# Openbook_Schematic.net
KiCad netlist of a schematic drawn in EAGLE
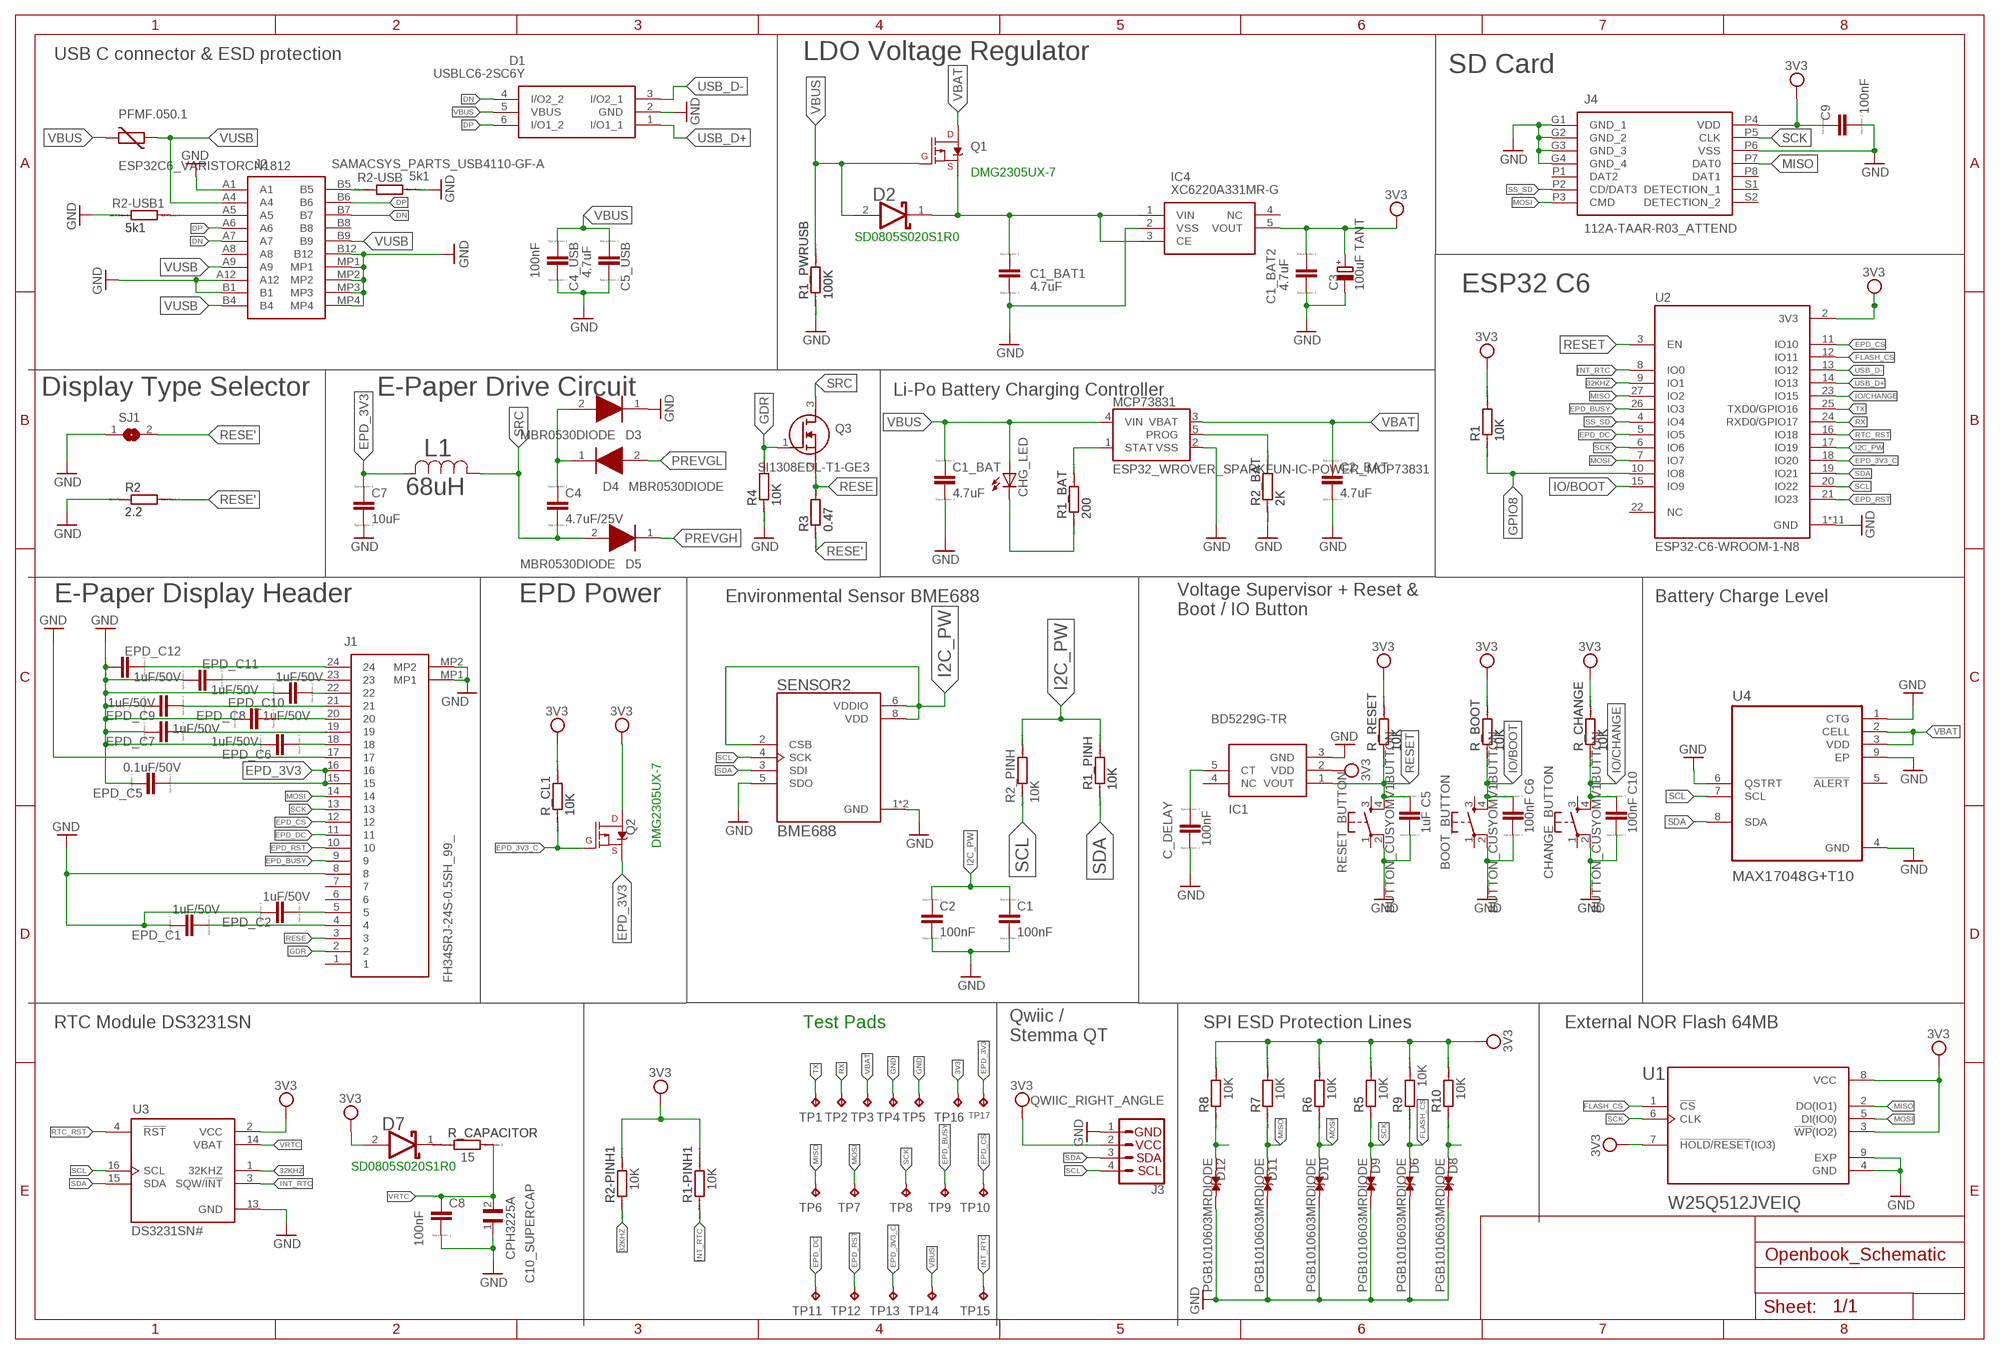
[diagram p0: schematic, sheet 1]

(export (version "E")
  (design (tool "Eeschema 10.0.6"))
  (components
    (comp (ref "BOOT_BUTTON")
      (value "BUTTON_CUSYOMV1BUTTON")
      (footprint "eagle-import:MYBUTTON")
      (libsource (lib "eagle-import") (part "BUTTON_CUSYOMV1BUTTON"))
    )
    (comp (ref "C1")
      (value "100nF")
      (footprint "eagle-import:EAGLE-LTSPICE_C0402")
      (libsource (lib "eagle-import") (part "ESP32_WROVER_EAGLE-LTSPICE_CC0402"))
    )
    (comp (ref "C1_BAT")
      (value "4.7uF")
      (footprint "eagle-import:EAGLE-LTSPICE_C0402")
      (libsource (lib "eagle-import") (part "ESP32_WROVER_EAGLE-LTSPICE_CC0402"))
    )
    (comp (ref "C1_BAT1")
      (value "4.7uF")
      (footprint "eagle-import:EAGLE-LTSPICE_C0402")
      (libsource (lib "eagle-import") (part "ESP32_WROVER_EAGLE-LTSPICE_CC0402"))
    )
    (comp (ref "C1_BAT2")
      (value "4.7uF")
      (footprint "eagle-import:EAGLE-LTSPICE_C0402")
      (libsource (lib "eagle-import") (part "ESP32_WROVER_EAGLE-LTSPICE_CC0402"))
    )
    (comp (ref "C2")
      (value "100nF")
      (footprint "eagle-import:EAGLE-LTSPICE_C0402")
      (libsource (lib "eagle-import") (part "ESP32_WROVER_EAGLE-LTSPICE_CC0402"))
    )
    (comp (ref "C2_BAT")
      (value "4.7uF")
      (footprint "eagle-import:EAGLE-LTSPICE_C0402")
      (libsource (lib "eagle-import") (part "ESP32_WROVER_EAGLE-LTSPICE_CC0402"))
    )
    (comp (ref "C3")
      (value "100uF TANT")
      (footprint "eagle-import:RCL_CT3528")
      (libsource (lib "eagle-import") (part "RCL_CPOL-EUCT3528"))
    )
    (comp (ref "C4")
      (value "4.7uF/25V")
      (footprint "eagle-import:EAGLE-LTSPICE_C0402")
      (libsource (lib "eagle-import") (part "ESP32_WROVER_EAGLE-LTSPICE_CC0402"))
    )
    (comp (ref "C4_USB")
      (value "100nF")
      (footprint "eagle-import:EAGLE-LTSPICE_C0402")
      (libsource (lib "eagle-import") (part "ESP32_WROVER_EAGLE-LTSPICE_CC0402"))
    )
    (comp (ref "C5")
      (value "1uF")
      (footprint "eagle-import:EAGLE-LTSPICE_C0402")
      (libsource (lib "eagle-import") (part "ESP32_WROVER_EAGLE-LTSPICE_CC0402"))
    )
    (comp (ref "C5_USB")
      (value "4.7uF")
      (footprint "eagle-import:EAGLE-LTSPICE_C0402")
      (libsource (lib "eagle-import") (part "ESP32_WROVER_EAGLE-LTSPICE_CC0402"))
    )
    (comp (ref "C6")
      (value "100nF")
      (footprint "eagle-import:EAGLE-LTSPICE_C0402")
      (libsource (lib "eagle-import") (part "ESP32_WROVER_EAGLE-LTSPICE_CC0402"))
    )
    (comp (ref "C7")
      (value "10uF")
      (footprint "eagle-import:EAGLE-LTSPICE_C0402")
      (libsource (lib "eagle-import") (part "ESP32_WROVER_EAGLE-LTSPICE_CC0402"))
    )
    (comp (ref "C8")
      (value "100nF")
      (footprint "eagle-import:EAGLE-LTSPICE_C0402")
      (libsource (lib "eagle-import") (part "ESP32_WROVER_EAGLE-LTSPICE_CC0402"))
    )
    (comp (ref "C9")
      (value "100nF")
      (footprint "eagle-import:EAGLE-LTSPICE_C0402")
      (libsource (lib "eagle-import") (part "ESP32_WROVER_EAGLE-LTSPICE_CC0402"))
    )
    (comp (ref "C10")
      (value "100nF")
      (footprint "eagle-import:EAGLE-LTSPICE_C0402")
      (libsource (lib "eagle-import") (part "ESP32_WROVER_EAGLE-LTSPICE_CC0402"))
    )
    (comp (ref "C10_SUPERCAP")
      (value "CPH3225A")
      (footprint "eagle-import:CAPCP3225X100N")
      (fields (field (name "MF") "Seiko Instruments"))
      (libsource (lib "eagle-import") (part "CPH3225A"))
    )
    (comp (ref "CHANGE_BUTTON")
      (value "BUTTON_CUSYOMV1BUTTON")
      (footprint "eagle-import:MYBUTTON")
      (libsource (lib "eagle-import") (part "BUTTON_CUSYOMV1BUTTON"))
    )
    (comp (ref "CHG_LED")
      (value "ADAFRUIT_LEDCHIP-LED0603")
      (footprint "eagle-import:ADAFRUIT_CHIP-LED0603")
      (libsource (lib "eagle-import") (part "ADAFRUIT_LEDCHIP-LED0603"))
    )
    (comp (ref "C_DELAY")
      (value "100nF")
      (footprint "eagle-import:EAGLE-LTSPICE_C0402")
      (libsource (lib "eagle-import") (part "ESP32_WROVER_EAGLE-LTSPICE_CC0402"))
    )
    (comp (ref "D1")
      (value "USBLC6-2SC6Y")
      (footprint "eagle-import:SOT95P280X145-6N")
      (fields (field (name "MF") "STMicroelectronics"))
      (libsource (lib "eagle-import") (part "USBLC6-2SC6Y"))
    )
    (comp (ref "D2")
      (value "SD0805S020S1R0")
      (footprint "eagle-import:ESP32_WROVER_AVX---SD0805S020S1R0_AVX_SD0805S020S1R0_0")
      (fields
        (field (name "DIGIKEY_PART_NUMBER") "478-7800-1-ND")
        (field (name "MF") "AVX")
        (field (name "MOUSER_PART_NUMBER") "581-SD0805S020S1R0")
      )
      (libsource (lib "eagle-import") (part "ESP32_WROVER_AVX---SD0805S020S1R0_AVX_SD0805S020S1R0_0_0AVX_SD0805S020S1R0_0_0"))
    )
    (comp (ref "D3")
      (value "MBR0530DIODE")
      (footprint "eagle-import:SOD3716X135N")
      (libsource (lib "eagle-import") (part "MBR0530DIODE"))
    )
    (comp (ref "D4")
      (value "MBR0530DIODE")
      (footprint "eagle-import:SOD3716X135N")
      (libsource (lib "eagle-import") (part "MBR0530DIODE"))
    )
    (comp (ref "D5")
      (value "MBR0530DIODE")
      (footprint "eagle-import:SOD3716X135N")
      (libsource (lib "eagle-import") (part "MBR0530DIODE"))
    )
    (comp (ref "D6")
      (value "PGB1010603MRDIODE")
      (footprint "eagle-import:DIOC1608X36N")
      (libsource (lib "eagle-import") (part "PGB1010603MRDIODE"))
    )
    (comp (ref "D7")
      (value "SD0805S020S1R0")
      (footprint "eagle-import:ESP32_WROVER_AVX---SD0805S020S1R0_AVX_SD0805S020S1R0_0")
      (fields
        (field (name "DIGIKEY_PART_NUMBER") "478-7800-1-ND")
        (field (name "MF") "AVX")
        (field (name "MOUSER_PART_NUMBER") "581-SD0805S020S1R0")
      )
      (libsource (lib "eagle-import") (part "ESP32_WROVER_AVX---SD0805S020S1R0_AVX_SD0805S020S1R0_0_0AVX_SD0805S020S1R0_0_0"))
    )
    (comp (ref "D8")
      (value "PGB1010603MRDIODE")
      (footprint "eagle-import:DIOC1608X36N")
      (libsource (lib "eagle-import") (part "PGB1010603MRDIODE"))
    )
    (comp (ref "D9")
      (value "PGB1010603MRDIODE")
      (footprint "eagle-import:DIOC1608X36N")
      (libsource (lib "eagle-import") (part "PGB1010603MRDIODE"))
    )
    (comp (ref "D10")
      (value "PGB1010603MRDIODE")
      (footprint "eagle-import:DIOC1608X36N")
      (libsource (lib "eagle-import") (part "PGB1010603MRDIODE"))
    )
    (comp (ref "D11")
      (value "PGB1010603MRDIODE")
      (footprint "eagle-import:DIOC1608X36N")
      (libsource (lib "eagle-import") (part "PGB1010603MRDIODE"))
    )
    (comp (ref "D12")
      (value "PGB1010603MRDIODE")
      (footprint "eagle-import:DIOC1608X36N")
      (libsource (lib "eagle-import") (part "PGB1010603MRDIODE"))
    )
    (comp (ref "EPD_C1")
      (value "1uF/50V")
      (footprint "eagle-import:EAGLE-LTSPICE_C0402")
      (libsource (lib "eagle-import") (part "ESP32_WROVER_EAGLE-LTSPICE_CC0402"))
    )
    (comp (ref "EPD_C2")
      (value "1uF/50V")
      (footprint "eagle-import:EAGLE-LTSPICE_C0402")
      (libsource (lib "eagle-import") (part "ESP32_WROVER_EAGLE-LTSPICE_CC0402"))
    )
    (comp (ref "EPD_C5")
      (value "0.1uF/50V")
      (footprint "eagle-import:EAGLE-LTSPICE_C0402")
      (libsource (lib "eagle-import") (part "ESP32_WROVER_EAGLE-LTSPICE_CC0402"))
    )
    (comp (ref "EPD_C6")
      (value "1uF/50V")
      (footprint "eagle-import:EAGLE-LTSPICE_C0402")
      (libsource (lib "eagle-import") (part "ESP32_WROVER_EAGLE-LTSPICE_CC0402"))
    )
    (comp (ref "EPD_C7")
      (value "1uF/50V")
      (footprint "eagle-import:EAGLE-LTSPICE_C0402")
      (libsource (lib "eagle-import") (part "ESP32_WROVER_EAGLE-LTSPICE_CC0402"))
    )
    (comp (ref "EPD_C8")
      (value "1uF/50V")
      (footprint "eagle-import:EAGLE-LTSPICE_C0402")
      (libsource (lib "eagle-import") (part "ESP32_WROVER_EAGLE-LTSPICE_CC0402"))
    )
    (comp (ref "EPD_C9")
      (value "1uF/50V")
      (footprint "eagle-import:EAGLE-LTSPICE_C0402")
      (libsource (lib "eagle-import") (part "ESP32_WROVER_EAGLE-LTSPICE_CC0402"))
    )
    (comp (ref "EPD_C10")
      (value "1uF/50V")
      (footprint "eagle-import:EAGLE-LTSPICE_C0402")
      (libsource (lib "eagle-import") (part "ESP32_WROVER_EAGLE-LTSPICE_CC0402"))
    )
    (comp (ref "EPD_C11")
      (value "1uF/50V")
      (footprint "eagle-import:EAGLE-LTSPICE_C0402")
      (libsource (lib "eagle-import") (part "ESP32_WROVER_EAGLE-LTSPICE_CC0402"))
    )
    (comp (ref "EPD_C12")
      (value "1uF/50V")
      (footprint "eagle-import:EAGLE-LTSPICE_C0402")
      (libsource (lib "eagle-import") (part "ESP32_WROVER_EAGLE-LTSPICE_CC0402"))
    )
    (comp (ref "IC1")
      (value "BD5229G-TR")
      (footprint "eagle-import:SOT95P280X125-5N")
      (fields (field (name "MOUSER_PART_NUMBER") "755-BD5229G-TR"))
      (libsource (lib "eagle-import") (part "BD5229G-TR"))
    )
    (comp (ref "IC4")
      (value "XC6220A331MR-G")
      (footprint "eagle-import:SOT95P280X120-5N")
      (fields (field (name "MOUSER_PART_NUMBER") "865-XC6220A331MR-G"))
      (libsource (lib "eagle-import") (part "XC6220A331MR-G"))
    )
    (comp (ref "J1")
      (value "FH34SRJ-24S-0.5SH_99_")
      (footprint "eagle-import:FH34SRJ24S05SH99")
      (fields
        (field (name "MANUFACTURER_PART_NUMBER") "FH34SRJ-24S-0.5SH(99)")
        (field (name "MOUSER_PART_NUMBER") "798-FH34SRJ24S05SH99")
      )
      (libsource (lib "eagle-import") (part "FH34SRJ-24S-0.5SH_99_"))
    )
    (comp (ref "J2")
      (value "SAMACSYS_PARTS_USB4110-GF-A")
      (footprint "eagle-import:SAMACSYS_PARTS_USB4110GFA")
      (fields
        (field (name "MANUFACTURER_PART_NUMBER") "USB4110-GF-A")
        (field (name "MOUSER_PART_NUMBER") "640-USB4110-GF-A")
      )
      (libsource (lib "eagle-import") (part "SAMACSYS_PARTS_USB4110-GF-A"))
    )
    (comp (ref "J3")
      (value "QWIIC_RIGHT_ANGLE")
      (footprint "eagle-import:JST04_1MM_RA")
      (libsource (lib "eagle-import") (part "QWIIC_CONNECTORJS-1MM"))
    )
    (comp (ref "J4")
      (value "112A-TAAR-R03_ATTEND")
      (footprint "eagle-import:112ATAARR03ATTEND")
      (fields (field (name "MANUFACTURER_PART_NUMBER") "112A-TAAR-R03 ATTEND"))
      (libsource (lib "eagle-import") (part "112A-TAAR-R03_ATTEND"))
    )
    (comp (ref "L1")
      (value "68uH")
      (footprint "eagle-import:IND_4828-WE-TPC_WRE")
      (fields
        (field (name "MANUFACTURER_PART_NUMBER") "744043680")
        (field (name "COPYRIGHT") "Copyright (C) 2024 Ultra Librarian. All rights reserved.")
      )
      (libsource (lib "eagle-import") (part "744043680IND_4828-WE-TPC_WRE"))
    )
    (comp (ref "MCP73831")
      (value "ESP32_WROVER_SPARKFUN-IC-POWER_MCP73831")
      (footprint "eagle-import:ESP32_WROVER_SPARKFUN-IC-POWER_SOT23-5")
      (libsource (lib "eagle-import") (part "ESP32_WROVER_SPARKFUN-IC-POWER_MCP73831"))
    )
    (comp (ref "PFMF.050.1")
      (value "ESP32C6_VARISTORCN1812")
      (footprint "eagle-import:ESP32C6_VARISTOR_CT_CN1812")
      (libsource (lib "eagle-import") (part "ESP32C6_VARISTORCN1812"))
    )
    (comp (ref "Q1")
      (value "20V/4.2A/52mΩ/1.4W")
      (footprint "eagle-import:ESP32_WROVER_SPARKFUN-DISCRETESEMI_SOT23-3")
      (libsource (lib "eagle-import") (part "ESP32_WROVER_SPARKFUN-DISCRETESEMI_MOSFET_PCH-DMG2305UX-7"))
    )
    (comp (ref "Q2")
      (value "20V/4.2A/52mΩ/1.4W")
      (footprint "eagle-import:ESP32_WROVER_SPARKFUN-DISCRETESEMI_SOT23-3")
      (libsource (lib "eagle-import") (part "ESP32_WROVER_SPARKFUN-DISCRETESEMI_MOSFET_PCH-DMG2305UX-7"))
    )
    (comp (ref "Q3")
      (value "SI1308EDL-T1-GE3")
      (footprint "eagle-import:SOT65P210X110-3N")
      (fields (field (name "MF") "Vishay Siliconix"))
      (libsource (lib "eagle-import") (part "SI1308EDL-T1-GE3"))
    )
    (comp (ref "R1")
      (value "10K")
      (footprint "eagle-import:ESP32_WROVER_EAGLE-LTSPICE_R0402")
      (libsource (lib "eagle-import") (part "ESP32_WROVER_EAGLE-LTSPICE_RR0402"))
    )
    (comp (ref "R1-PINH1")
      (value "10K")
      (footprint "eagle-import:ESP32_WROVER_EAGLE-LTSPICE_R0402")
      (libsource (lib "eagle-import") (part "ESP32_WROVER_EAGLE-LTSPICE_RR0402"))
    )
    (comp (ref "R1_BAT")
      (value "200")
      (footprint "eagle-import:ESP32_WROVER_EAGLE-LTSPICE_R0402")
      (libsource (lib "eagle-import") (part "ESP32_WROVER_EAGLE-LTSPICE_RR0402"))
    )
    (comp (ref "R1_PINH")
      (value "10K")
      (footprint "eagle-import:ESP32_WROVER_EAGLE-LTSPICE_R0402")
      (libsource (lib "eagle-import") (part "ESP32_WROVER_EAGLE-LTSPICE_RR0402"))
    )
    (comp (ref "R1_PWRUSB")
      (value "100K")
      (footprint "eagle-import:ESP32_WROVER_EAGLE-LTSPICE_R0402")
      (libsource (lib "eagle-import") (part "ESP32_WROVER_EAGLE-LTSPICE_RR0402"))
    )
    (comp (ref "R2")
      (value "2.2")
      (footprint "eagle-import:ESP32_WROVER_EAGLE-LTSPICE_R0402")
      (libsource (lib "eagle-import") (part "ESP32_WROVER_EAGLE-LTSPICE_RR0402"))
    )
    (comp (ref "R2-PINH1")
      (value "10K")
      (footprint "eagle-import:ESP32_WROVER_EAGLE-LTSPICE_R0402")
      (libsource (lib "eagle-import") (part "ESP32_WROVER_EAGLE-LTSPICE_RR0402"))
    )
    (comp (ref "R2-USB")
      (value "5k1")
      (footprint "eagle-import:ESP32_WROVER_EAGLE-LTSPICE_R0402")
      (libsource (lib "eagle-import") (part "ESP32_WROVER_EAGLE-LTSPICE_RR0402"))
    )
    (comp (ref "R2-USB1")
      (value "5k1")
      (footprint "eagle-import:ESP32_WROVER_EAGLE-LTSPICE_R0402")
      (libsource (lib "eagle-import") (part "ESP32_WROVER_EAGLE-LTSPICE_RR0402"))
    )
    (comp (ref "R2_BAT")
      (value "2K")
      (footprint "eagle-import:ESP32_WROVER_EAGLE-LTSPICE_R0402")
      (libsource (lib "eagle-import") (part "ESP32_WROVER_EAGLE-LTSPICE_RR0402"))
    )
    (comp (ref "R2_PINH")
      (value "10K")
      (footprint "eagle-import:ESP32_WROVER_EAGLE-LTSPICE_R0402")
      (libsource (lib "eagle-import") (part "ESP32_WROVER_EAGLE-LTSPICE_RR0402"))
    )
    (comp (ref "R3")
      (value "0.47")
      (footprint "eagle-import:ESP32_WROVER_EAGLE-LTSPICE_R0402")
      (libsource (lib "eagle-import") (part "ESP32_WROVER_EAGLE-LTSPICE_RR0402"))
    )
    (comp (ref "R4")
      (value "10K")
      (footprint "eagle-import:ESP32_WROVER_EAGLE-LTSPICE_R0402")
      (libsource (lib "eagle-import") (part "ESP32_WROVER_EAGLE-LTSPICE_RR0402"))
    )
    (comp (ref "R5")
      (value "10K")
      (footprint "eagle-import:ESP32_WROVER_EAGLE-LTSPICE_R0402")
      (libsource (lib "eagle-import") (part "ESP32_WROVER_EAGLE-LTSPICE_RR0402"))
    )
    (comp (ref "R6")
      (value "10K")
      (footprint "eagle-import:ESP32_WROVER_EAGLE-LTSPICE_R0402")
      (libsource (lib "eagle-import") (part "ESP32_WROVER_EAGLE-LTSPICE_RR0402"))
    )
    (comp (ref "R7")
      (value "10K")
      (footprint "eagle-import:ESP32_WROVER_EAGLE-LTSPICE_R0402")
      (libsource (lib "eagle-import") (part "ESP32_WROVER_EAGLE-LTSPICE_RR0402"))
    )
    (comp (ref "R8")
      (value "10K")
      (footprint "eagle-import:ESP32_WROVER_EAGLE-LTSPICE_R0402")
      (libsource (lib "eagle-import") (part "ESP32_WROVER_EAGLE-LTSPICE_RR0402"))
    )
    (comp (ref "R9")
      (value "10K")
      (footprint "eagle-import:ESP32_WROVER_EAGLE-LTSPICE_R0402")
      (libsource (lib "eagle-import") (part "ESP32_WROVER_EAGLE-LTSPICE_RR0402"))
    )
    (comp (ref "R10")
      (value "10K")
      (footprint "eagle-import:ESP32_WROVER_EAGLE-LTSPICE_R0402")
      (libsource (lib "eagle-import") (part "ESP32_WROVER_EAGLE-LTSPICE_RR0402"))
    )
    (comp (ref "RESET_BUTTON")
      (value "BUTTON_CUSYOMV1BUTTON")
      (footprint "eagle-import:MYBUTTON")
      (libsource (lib "eagle-import") (part "BUTTON_CUSYOMV1BUTTON"))
    )
    (comp (ref "R_BOOT")
      (value "10K")
      (footprint "eagle-import:ESP32_WROVER_EAGLE-LTSPICE_R0402")
      (libsource (lib "eagle-import") (part "ESP32_WROVER_EAGLE-LTSPICE_RR0402"))
    )
    (comp (ref "R_CAPACITOR")
      (value "15")
      (footprint "eagle-import:ESP32_WROVER_EAGLE-LTSPICE_R0402")
      (libsource (lib "eagle-import") (part "ESP32_WROVER_EAGLE-LTSPICE_RR0402"))
    )
    (comp (ref "R_CHANGE")
      (value "10K")
      (footprint "eagle-import:ESP32_WROVER_EAGLE-LTSPICE_R0402")
      (libsource (lib "eagle-import") (part "ESP32_WROVER_EAGLE-LTSPICE_RR0402"))
    )
    (comp (ref "R_CL1")
      (value "10K")
      (footprint "eagle-import:ESP32_WROVER_EAGLE-LTSPICE_R0402")
      (libsource (lib "eagle-import") (part "ESP32_WROVER_EAGLE-LTSPICE_RR0402"))
    )
    (comp (ref "R_RESET")
      (value "10K")
      (footprint "eagle-import:ESP32_WROVER_EAGLE-LTSPICE_R0402")
      (libsource (lib "eagle-import") (part "ESP32_WROVER_EAGLE-LTSPICE_RR0402"))
    )
    (comp (ref "SENSOR2")
      (value "BME688")
      (footprint "eagle-import:ESP32_WROVER_BME680_PSON80P300X300X100-8N")
      (fields (field (name "MF") "Bosch Sensortec") (field (name "MP") "BME680"))
      (libsource (lib "eagle-import") (part "ESP32_WROVER_BME680_BME680"))
    )
    (comp (ref "SJ1") (value "SJ") (footprint "eagle-import:SJ") (libsource (lib "eagle-import") (part "SJ")))
    (comp (ref "TP1")
      (value "TPTP20R")
      (footprint "eagle-import:TP20R")
      (libsource (lib "eagle-import") (part "TPTP20R"))
    )
    (comp (ref "TP2")
      (value "TPTP20R")
      (footprint "eagle-import:TP20R")
      (libsource (lib "eagle-import") (part "TPTP20R"))
    )
    (comp (ref "TP3")
      (value "TPTP20R")
      (footprint "eagle-import:TP20R")
      (libsource (lib "eagle-import") (part "TPTP20R"))
    )
    (comp (ref "TP4")
      (value "TPTP20R")
      (footprint "eagle-import:TP20R")
      (libsource (lib "eagle-import") (part "TPTP20R"))
    )
    (comp (ref "TP5")
      (value "TPTP20R")
      (footprint "eagle-import:TP20R")
      (libsource (lib "eagle-import") (part "TPTP20R"))
    )
    (comp (ref "TP6")
      (value "TPTP20R")
      (footprint "eagle-import:TP20R")
      (libsource (lib "eagle-import") (part "TPTP20R"))
    )
    (comp (ref "TP7")
      (value "TPTP20R")
      (footprint "eagle-import:TP20R")
      (libsource (lib "eagle-import") (part "TPTP20R"))
    )
    (comp (ref "TP8")
      (value "TPTP20R")
      (footprint "eagle-import:TP20R")
      (libsource (lib "eagle-import") (part "TPTP20R"))
    )
    (comp (ref "TP9")
      (value "TPTP20R")
      (footprint "eagle-import:TP20R")
      (libsource (lib "eagle-import") (part "TPTP20R"))
    )
    (comp (ref "TP10")
      (value "TPTP20R")
      (footprint "eagle-import:TP20R")
      (libsource (lib "eagle-import") (part "TPTP20R"))
    )
    (comp (ref "TP11")
      (value "TPTP20R")
      (footprint "eagle-import:TP20R")
      (libsource (lib "eagle-import") (part "TPTP20R"))
    )
    (comp (ref "TP12")
      (value "TPTP20R")
      (footprint "eagle-import:TP20R")
      (libsource (lib "eagle-import") (part "TPTP20R"))
    )
    (comp (ref "TP13")
      (value "TPTP20R")
      (footprint "eagle-import:TP20R")
      (libsource (lib "eagle-import") (part "TPTP20R"))
    )
    (comp (ref "TP14")
      (value "TPTP20R")
      (footprint "eagle-import:TP20R")
      (libsource (lib "eagle-import") (part "TPTP20R"))
    )
    (comp (ref "TP15")
      (value "TPTP20R")
      (footprint "eagle-import:TP20R")
      (libsource (lib "eagle-import") (part "TPTP20R"))
    )
    (comp (ref "TP16")
      (value "TPTP20R")
      (footprint "eagle-import:TP20R")
      (libsource (lib "eagle-import") (part "TPTP20R"))
    )
    (comp (ref "TP17")
      (value "TPTP20R")
      (footprint "eagle-import:TP20R")
      (libsource (lib "eagle-import") (part "TPTP20R"))
    )
    (comp (ref "U1")
      (value "W25Q512JVEIQ")
      (footprint "eagle-import:SON127P600X800X80-9N")
      (fields (field (name "MF") "Winbond Electronics"))
      (libsource (lib "eagle-import") (part "W25Q512JVEIQ"))
    )
    (comp (ref "U2")
      (value "ESP32-C6-WROOM-1-N8")
      (footprint "eagle-import:XCVR_ESP32-C6-WROOM-1-N8")
      (fields (field (name "MF") "Espressif Systems"))
      (libsource (lib "eagle-import") (part "ESP32-C6-WROOM-1-N8"))
    )
    (comp (ref "U3")
      (value "DS3231SN#")
      (footprint "eagle-import:SOIC127P1032X265-16N")
      (fields (field (name "MF") "Analog Devices"))
      (libsource (lib "eagle-import") (part "DS3231SN#"))
    )
    (comp (ref "U4")
      (value "MAX17048G+T10")
      (footprint "eagle-import:SON50P200X200X80-9N")
      (fields (field (name "MF") "Analog Devices"))
      (libsource (lib "eagle-import") (part "MAX17048G+T10"))
    )
  )
  (nets
    (net (code "1") (name "3V3") (class "Default")
      (node (ref "C1_BAT2") (pin "1") (pinfunction "1_1") (pintype "passive"))
      (node (ref "C3") (pin "+") (pinfunction "+_+") (pintype "passive"))
      (node (ref "C9") (pin "1") (pinfunction "1_1") (pintype "passive"))
      (node (ref "D7") (pin "2") (pinfunction "ANODE_2") (pintype "bidirectional"))
      (node (ref "IC1") (pin "2") (pinfunction "VDD_2") (pintype "bidirectional"))
      (node (ref "IC4") (pin "5") (pinfunction "VOUT_5") (pintype "bidirectional"))
      (node (ref "J3") (pin "2") (pinfunction "2_2") (pintype "power_in"))
      (node (ref "J4") (pin "P4") (pinfunction "VDD_P4") (pintype "bidirectional"))
      (node (ref "Q2") (pin "3") (pinfunction "D_3") (pintype "bidirectional"))
      (node (ref "R1") (pin "2") (pinfunction "2_2") (pintype "passive"))
      (node (ref "R1-PINH1") (pin "2") (pinfunction "2_2") (pintype "passive"))
      (node (ref "R10") (pin "2") (pinfunction "2_2") (pintype "passive"))
      (node (ref "R2-PINH1") (pin "2") (pinfunction "2_2") (pintype "passive"))
      (node (ref "R5") (pin "2") (pinfunction "2_2") (pintype "passive"))
      (node (ref "R6") (pin "2") (pinfunction "2_2") (pintype "passive"))
      (node (ref "R7") (pin "2") (pinfunction "2_2") (pintype "passive"))
      (node (ref "R8") (pin "2") (pinfunction "2_2") (pintype "passive"))
      (node (ref "R9") (pin "2") (pinfunction "2_2") (pintype "passive"))
      (node (ref "R_BOOT") (pin "2") (pinfunction "2_2") (pintype "passive"))
      (node (ref "R_CHANGE") (pin "2") (pinfunction "2_2") (pintype "passive"))
      (node (ref "R_CL1") (pin "2") (pinfunction "2_2") (pintype "passive"))
      (node (ref "R_RESET") (pin "2") (pinfunction "2_2") (pintype "passive"))
      (node (ref "TP16") (pin "TP") (pinfunction "TP_TP") (pintype "input"))
      (node (ref "U1") (pin "3") (pinfunction "~{WP}(IO2)_3") (pintype "bidirectional"))
      (node (ref "U1") (pin "7") (pinfunction "~{HOLD}/~{RESET}(IO3)_7") (pintype "bidirectional"))
      (node (ref "U1") (pin "8") (pinfunction "VCC_8") (pintype "power_in"))
      (node (ref "U2") (pin "2") (pinfunction "3V3_2") (pintype "power_in"))
      (node (ref "U3") (pin "2") (pinfunction "VCC_2") (pintype "power_in"))
    )
    (net (code "2") (name "32KHZ") (class "Default")
      (node (ref "R2-PINH1") (pin "1") (pinfunction "1_1") (pintype "passive"))
      (node (ref "U2") (pin "9") (pinfunction "IO1_9") (pintype "bidirectional"))
      (node (ref "U3") (pin "1") (pinfunction "32KHZ_1") (pintype "output"))
    )
    (net (code "3") (name "DN") (class "Default")
      (node (ref "D1") (pin "4") (pinfunction "I/O2_2_4") (pintype "bidirectional"))
      (node (ref "J2") (pin "A7") (pinfunction "A7_A7") (pintype "bidirectional"))
      (node (ref "J2") (pin "B7") (pinfunction "B7_B7") (pintype "bidirectional"))
    )
    (net (code "4") (name "DP") (class "Default")
      (node (ref "D1") (pin "6") (pinfunction "I/O1_2_6") (pintype "bidirectional"))
      (node (ref "J2") (pin "A6") (pinfunction "A6_A6") (pintype "bidirectional"))
      (node (ref "J2") (pin "B6") (pinfunction "B6_B6") (pintype "bidirectional"))
    )
    (net (code "5") (name "EPD_3V3") (class "Default")
      (node (ref "C7") (pin "1") (pinfunction "1_1") (pintype "passive"))
      (node (ref "EPD_C5") (pin "2") (pinfunction "2_2") (pintype "passive"))
      (node (ref "J1") (pin "15") (pinfunction "15_15") (pintype "bidirectional"))
      (node (ref "J1") (pin "16") (pinfunction "16_16") (pintype "bidirectional"))
      (node (ref "L1") (pin "2") (pinfunction "2_2") (pintype "passive"))
      (node (ref "Q2") (pin "2") (pinfunction "S_2") (pintype "bidirectional"))
      (node (ref "TP17") (pin "TP") (pinfunction "TP_TP") (pintype "input"))
    )
    (net (code "6") (name "EPD_3V3_C") (class "Default")
      (node (ref "Q2") (pin "1") (pinfunction "G_1") (pintype "bidirectional"))
      (node (ref "R_CL1") (pin "1") (pinfunction "1_1") (pintype "passive"))
      (node (ref "TP13") (pin "TP") (pinfunction "TP_TP") (pintype "input"))
      (node (ref "U2") (pin "18") (pinfunction "IO20_18") (pintype "bidirectional"))
    )
    (net (code "7") (name "EPD_BUSY") (class "Default")
      (node (ref "J1") (pin "9") (pinfunction "9_9") (pintype "bidirectional"))
      (node (ref "TP9") (pin "TP") (pinfunction "TP_TP") (pintype "input"))
      (node (ref "U2") (pin "26") (pinfunction "IO3_26") (pintype "bidirectional"))
    )
    (net (code "8") (name "EPD_CS") (class "Default")
      (node (ref "J1") (pin "12") (pinfunction "12_12") (pintype "bidirectional"))
      (node (ref "TP10") (pin "TP") (pinfunction "TP_TP") (pintype "input"))
      (node (ref "U2") (pin "11") (pinfunction "IO10_11") (pintype "bidirectional"))
    )
    (net (code "9") (name "EPD_DC") (class "Default")
      (node (ref "J1") (pin "11") (pinfunction "11_11") (pintype "bidirectional"))
      (node (ref "TP11") (pin "TP") (pinfunction "TP_TP") (pintype "input"))
      (node (ref "U2") (pin "5") (pinfunction "IO5_5") (pintype "bidirectional"))
    )
    (net (code "10") (name "EPD_RST") (class "Default")
      (node (ref "J1") (pin "10") (pinfunction "10_10") (pintype "bidirectional"))
      (node (ref "TP12") (pin "TP") (pinfunction "TP_TP") (pintype "input"))
      (node (ref "U2") (pin "21") (pinfunction "IO23_21") (pintype "bidirectional"))
    )
    (net (code "11") (name "FLASH_CS") (class "Default")
      (node (ref "D6") (pin "1") (pinfunction "1_1") (pintype "passive"))
      (node (ref "R9") (pin "1") (pinfunction "1_1") (pintype "passive"))
      (node (ref "U1") (pin "1") (pinfunction "~{CS}_1") (pintype "input"))
      (node (ref "U2") (pin "12") (pinfunction "IO11_12") (pintype "bidirectional"))
    )
    (net (code "12") (name "GDR") (class "Default")
      (node (ref "J1") (pin "2") (pinfunction "2_2") (pintype "bidirectional"))
      (node (ref "Q3") (pin "1") (pinfunction "G_1") (pintype "bidirectional"))
      (node (ref "R4") (pin "2") (pinfunction "2_2") (pintype "passive"))
    )
    (net (code "13") (name "GND") (class "Default")
      (node (ref "BOOT_BUTTON") (pin "2") (pinfunction "2_2") (pintype "passive"))
      (node (ref "C1") (pin "2") (pinfunction "2_2") (pintype "passive"))
      (node (ref "C10") (pin "2") (pinfunction "2_2") (pintype "passive"))
      (node (ref "C10_SUPERCAP") (pin "1") (pinfunction "1_1") (pintype "passive"))
      (node (ref "C1_BAT") (pin "2") (pinfunction "2_2") (pintype "passive"))
      (node (ref "C1_BAT1") (pin "2") (pinfunction "2_2") (pintype "passive"))
      (node (ref "C1_BAT2") (pin "2") (pinfunction "2_2") (pintype "passive"))
      (node (ref "C2") (pin "2") (pinfunction "2_2") (pintype "passive"))
      (node (ref "C2_BAT") (pin "2") (pinfunction "2_2") (pintype "passive"))
      (node (ref "C3") (pin "-") (pinfunction "-_-") (pintype "passive"))
      (node (ref "C4_USB") (pin "2") (pinfunction "2_2") (pintype "passive"))
      (node (ref "C5") (pin "2") (pinfunction "2_2") (pintype "passive"))
      (node (ref "C5_USB") (pin "2") (pinfunction "2_2") (pintype "passive"))
      (node (ref "C6") (pin "2") (pinfunction "2_2") (pintype "passive"))
      (node (ref "C7") (pin "2") (pinfunction "2_2") (pintype "passive"))
      (node (ref "C8") (pin "2") (pinfunction "2_2") (pintype "passive"))
      (node (ref "C9") (pin "2") (pinfunction "2_2") (pintype "passive"))
      (node (ref "CHANGE_BUTTON") (pin "2") (pinfunction "2_2") (pintype "passive"))
      (node (ref "C_DELAY") (pin "2") (pinfunction "2_2") (pintype "passive"))
      (node (ref "D1") (pin "2") (pinfunction "GND_2") (pintype "bidirectional"))
      (node (ref "D10") (pin "2") (pinfunction "2_2") (pintype "passive"))
      (node (ref "D11") (pin "2") (pinfunction "2_2") (pintype "passive"))
      (node (ref "D12") (pin "2") (pinfunction "2_2") (pintype "passive"))
      (node (ref "D3") (pin "1") (pinfunction "K_1") (pintype "bidirectional"))
      (node (ref "D6") (pin "2") (pinfunction "2_2") (pintype "passive"))
      (node (ref "D8") (pin "2") (pinfunction "2_2") (pintype "passive"))
      (node (ref "D9") (pin "2") (pinfunction "2_2") (pintype "passive"))
      (node (ref "EPD_C1") (pin "1") (pinfunction "1_1") (pintype "passive"))
      (node (ref "EPD_C10") (pin "1") (pinfunction "1_1") (pintype "passive"))
      (node (ref "EPD_C11") (pin "1") (pinfunction "1_1") (pintype "passive"))
      (node (ref "EPD_C12") (pin "1") (pinfunction "1_1") (pintype "passive"))
      (node (ref "EPD_C2") (pin "1") (pinfunction "1_1") (pintype "passive"))
      (node (ref "EPD_C5") (pin "1") (pinfunction "1_1") (pintype "passive"))
      (node (ref "EPD_C6") (pin "1") (pinfunction "1_1") (pintype "passive"))
      (node (ref "EPD_C7") (pin "1") (pinfunction "1_1") (pintype "passive"))
      (node (ref "EPD_C8") (pin "1") (pinfunction "1_1") (pintype "passive"))
      (node (ref "EPD_C9") (pin "1") (pinfunction "1_1") (pintype "passive"))
      (node (ref "IC1") (pin "3") (pinfunction "GND_3") (pintype "bidirectional"))
      (node (ref "IC4") (pin "2") (pinfunction "VSS_2") (pintype "bidirectional"))
      (node (ref "J1") (pin "17") (pinfunction "17_17") (pintype "bidirectional"))
      (node (ref "J1") (pin "8") (pinfunction "8_8") (pintype "bidirectional"))
      (node (ref "J1") (pin "MP1") (pinfunction "MP1_MP1") (pintype "bidirectional"))
      (node (ref "J1") (pin "MP2") (pinfunction "MP2_MP2") (pintype "bidirectional"))
      (node (ref "J2") (pin "A1") (pinfunction "A1_A1") (pintype "bidirectional"))
      (node (ref "J2") (pin "A12") (pinfunction "A12_A12") (pintype "bidirectional"))
      (node (ref "J2") (pin "B1") (pinfunction "B1_B1") (pintype "bidirectional"))
      (node (ref "J2") (pin "B12") (pinfunction "B12_B12") (pintype "bidirectional"))
      (node (ref "J2") (pin "MP1") (pinfunction "MP1_MP1") (pintype "bidirectional"))
      (node (ref "J2") (pin "MP2") (pinfunction "MP2_MP2") (pintype "bidirectional"))
      (node (ref "J2") (pin "MP3") (pinfunction "MP3_MP3") (pintype "bidirectional"))
      (node (ref "J2") (pin "MP4") (pinfunction "MP4_MP4") (pintype "bidirectional"))
      (node (ref "J3") (pin "1") (pinfunction "1_1") (pintype "power_in"))
      (node (ref "J4") (pin "G1") (pinfunction "GND_1_G1") (pintype "bidirectional"))
      (node (ref "J4") (pin "G2") (pinfunction "GND_2_G2") (pintype "bidirectional"))
      (node (ref "J4") (pin "G3") (pinfunction "GND_3_G3") (pintype "bidirectional"))
      (node (ref "J4") (pin "G4") (pinfunction "GND_4_G4") (pintype "bidirectional"))
      (node (ref "J4") (pin "P6") (pinfunction "VSS_P6") (pintype "bidirectional"))
      (node (ref "MCP73831") (pin "2") (pinfunction "VSS_2") (pintype "power_in"))
      (node (ref "R1_PWRUSB") (pin "1") (pinfunction "1_1") (pintype "passive"))
      (node (ref "R2") (pin "1") (pinfunction "1_1") (pintype "passive"))
      (node (ref "R2-USB") (pin "2") (pinfunction "2_2") (pintype "passive"))
      (node (ref "R2-USB1") (pin "1") (pinfunction "1_1") (pintype "passive"))
      (node (ref "R2_BAT") (pin "1") (pinfunction "1_1") (pintype "passive"))
      (node (ref "R4") (pin "1") (pinfunction "1_1") (pintype "passive"))
      (node (ref "RESET_BUTTON") (pin "2") (pinfunction "2_2") (pintype "passive"))
      (node (ref "SENSOR2") (pin "1") (pinfunction "GND_1") (pintype "power_in"))
      (node (ref "SENSOR2") (pin "5") (pinfunction "SDO_5") (pintype "bidirectional"))
      (node (ref "SENSOR2") (pin "7") (pinfunction "GND_7") (pintype "power_in"))
      (node (ref "SJ1") (pin "1") (pinfunction "1_1") (pintype "passive"))
      (node (ref "TP4") (pin "TP") (pinfunction "TP_TP") (pintype "input"))
      (node (ref "TP5") (pin "TP") (pinfunction "TP_TP") (pintype "input"))
      (node (ref "U1") (pin "4") (pinfunction "GND_4") (pintype "power_in"))
      (node (ref "U1") (pin "9") (pinfunction "EXP_9") (pintype "passive"))
      (node (ref "U2") (pin "1") (pinfunction "GND_1") (pintype "power_in"))
      (node (ref "U2") (pin "28") (pinfunction "GND_28") (pintype "power_in"))
      (node (ref "U2") (pin "29_1") (pinfunction "GND_29_1") (pintype "power_in"))
      (node (ref "U2") (pin "29_2") (pinfunction "GND_29_2") (pintype "power_in"))
      (node (ref "U2") (pin "29_3") (pinfunction "GND_29_3") (pintype "power_in"))
      (node (ref "U2") (pin "29_4") (pinfunction "GND_29_4") (pintype "power_in"))
      (node (ref "U2") (pin "29_5") (pinfunction "GND_29_5") (pintype "power_in"))
      (node (ref "U2") (pin "29_6") (pinfunction "GND_29_6") (pintype "power_in"))
      (node (ref "U2") (pin "29_7") (pinfunction "GND_29_7") (pintype "power_in"))
      (node (ref "U2") (pin "29_8") (pinfunction "GND_29_8") (pintype "power_in"))
      (node (ref "U2") (pin "29_9") (pinfunction "GND_29_9") (pintype "power_in"))
      (node (ref "U3") (pin "13") (pinfunction "GND_13") (pintype "power_in"))
      (node (ref "U4") (pin "1") (pinfunction "CTG_1") (pintype "power_in"))
      (node (ref "U4") (pin "4") (pinfunction "GND_4") (pintype "power_in"))
      (node (ref "U4") (pin "6") (pinfunction "QSTRT_6") (pintype "input"))
      (node (ref "U4") (pin "9") (pinfunction "EP_9") (pintype "power_in"))
    )
    (net (code "14") (name "GPIO8") (class "Default")
      (node (ref "R1") (pin "1") (pinfunction "1_1") (pintype "passive"))
      (node (ref "U2") (pin "10") (pinfunction "IO8_10") (pintype "bidirectional"))
    )
    (net (code "15") (name "I2C_PW") (class "Default")
      (node (ref "C1") (pin "1") (pinfunction "1_1") (pintype "passive"))
      (node (ref "C2") (pin "1") (pinfunction "1_1") (pintype "passive"))
      (node (ref "R1_PINH") (pin "2") (pinfunction "2_2") (pintype "passive"))
      (node (ref "R2_PINH") (pin "2") (pinfunction "2_2") (pintype "passive"))
      (node (ref "SENSOR2") (pin "2") (pinfunction "CSB_2") (pintype "input"))
      (node (ref "SENSOR2") (pin "6") (pinfunction "VDDIO_6") (pintype "power_in"))
      (node (ref "SENSOR2") (pin "8") (pinfunction "VDD_8") (pintype "power_in"))
      (node (ref "U2") (pin "17") (pinfunction "IO19_17") (pintype "bidirectional"))
    )
    (net (code "16") (name "INT_RTC") (class "Default")
      (node (ref "R1-PINH1") (pin "1") (pinfunction "1_1") (pintype "passive"))
      (node (ref "TP15") (pin "TP") (pinfunction "TP_TP") (pintype "input"))
      (node (ref "U2") (pin "8") (pinfunction "IO0_8") (pintype "bidirectional"))
      (node (ref "U3") (pin "3") (pinfunction "SQW/~{INT}_3") (pintype "output"))
    )
    (net (code "17") (name "IO{slash}BOOT") (class "Default")
      (node (ref "BOOT_BUTTON") (pin "4") (pinfunction "4_4") (pintype "passive"))
      (node (ref "C6") (pin "1") (pinfunction "1_1") (pintype "passive"))
      (node (ref "R_BOOT") (pin "1") (pinfunction "1_1") (pintype "passive"))
      (node (ref "U2") (pin "15") (pinfunction "IO9_15") (pintype "bidirectional"))
    )
    (net (code "18") (name "IO{slash}CHANGE") (class "Default")
      (node (ref "C10") (pin "1") (pinfunction "1_1") (pintype "passive"))
      (node (ref "CHANGE_BUTTON") (pin "4") (pinfunction "4_4") (pintype "passive"))
      (node (ref "R_CHANGE") (pin "1") (pinfunction "1_1") (pintype "passive"))
      (node (ref "U2") (pin "23") (pinfunction "IO15_23") (pintype "bidirectional"))
    )
    (net (code "19") (name "MISO") (class "Default")
      (node (ref "D11") (pin "1") (pinfunction "1_1") (pintype "passive"))
      (node (ref "J4") (pin "P7") (pinfunction "DAT0_P7") (pintype "bidirectional"))
      (node (ref "R7") (pin "1") (pinfunction "1_1") (pintype "passive"))
      (node (ref "TP6") (pin "TP") (pinfunction "TP_TP") (pintype "input"))
      (node (ref "U1") (pin "2") (pinfunction "DO(IO1)_2") (pintype "bidirectional"))
      (node (ref "U2") (pin "27") (pinfunction "IO2_27") (pintype "bidirectional"))
    )
    (net (code "20") (name "MOSI") (class "Default")
      (node (ref "D10") (pin "1") (pinfunction "1_1") (pintype "passive"))
      (node (ref "J1") (pin "14") (pinfunction "14_14") (pintype "bidirectional"))
      (node (ref "J4") (pin "P3") (pinfunction "CMD_P3") (pintype "bidirectional"))
      (node (ref "R6") (pin "1") (pinfunction "1_1") (pintype "passive"))
      (node (ref "TP7") (pin "TP") (pinfunction "TP_TP") (pintype "input"))
      (node (ref "U1") (pin "5") (pinfunction "DI(IO0)_5") (pintype "bidirectional"))
      (node (ref "U2") (pin "7") (pinfunction "IO7_7") (pintype "bidirectional"))
    )
    (net (code "21") (name "Net-(CHG_LED-PadC)") (class "Default")
      (node (ref "CHG_LED") (pin "C") (pinfunction "C_C") (pintype "passive"))
      (node (ref "R1_BAT") (pin "1") (pinfunction "1_1") (pintype "passive"))
    )
    (net (code "22") (name "Net-(D2-CATHODE)") (class "Default")
      (node (ref "C1_BAT1") (pin "1") (pinfunction "1_1") (pintype "passive"))
      (node (ref "D2") (pin "1") (pinfunction "CATHODE_1") (pintype "bidirectional"))
      (node (ref "IC4") (pin "1") (pinfunction "VIN_1") (pintype "bidirectional"))
      (node (ref "IC4") (pin "3") (pinfunction "CE_3") (pintype "bidirectional"))
      (node (ref "Q1") (pin "2") (pinfunction "S_2") (pintype "bidirectional"))
    )
    (net (code "23") (name "Net-(D3-A)") (class "Default")
      (node (ref "C4") (pin "1") (pinfunction "1_1") (pintype "passive"))
      (node (ref "D3") (pin "2") (pinfunction "A_2") (pintype "bidirectional"))
      (node (ref "D4") (pin "1") (pinfunction "K_1") (pintype "bidirectional"))
    )
    (net (code "24") (name "Net-(D7-CATHODE)") (class "Default")
      (node (ref "D7") (pin "1") (pinfunction "CATHODE_1") (pintype "bidirectional"))
      (node (ref "R_CAPACITOR") (pin "1") (pinfunction "1_1") (pintype "passive"))
    )
    (net (code "25") (name "Net-(D8-Pad1)") (class "Default")
      (node (ref "D8") (pin "1") (pinfunction "1_1") (pintype "passive"))
      (node (ref "R10") (pin "1") (pinfunction "1_1") (pintype "passive"))
    )
    (net (code "26") (name "Net-(D12-Pad1)") (class "Default")
      (node (ref "D12") (pin "1") (pinfunction "1_1") (pintype "passive"))
      (node (ref "R8") (pin "1") (pinfunction "1_1") (pintype "passive"))
    )
    (net (code "27") (name "Net-(EPD_C1-Pad2)") (class "Default")
      (node (ref "EPD_C1") (pin "2") (pinfunction "2_2") (pintype "passive"))
      (node (ref "J1") (pin "4") (pinfunction "4_4") (pintype "bidirectional"))
    )
    (net (code "28") (name "Net-(EPD_C2-Pad2)") (class "Default")
      (node (ref "EPD_C2") (pin "2") (pinfunction "2_2") (pintype "passive"))
      (node (ref "J1") (pin "5") (pinfunction "5_5") (pintype "bidirectional"))
    )
    (net (code "29") (name "Net-(EPD_C6-Pad2)") (class "Default")
      (node (ref "EPD_C6") (pin "2") (pinfunction "2_2") (pintype "passive"))
      (node (ref "J1") (pin "18") (pinfunction "18_18") (pintype "bidirectional"))
    )
    (net (code "30") (name "Net-(EPD_C7-Pad2)") (class "Default")
      (node (ref "EPD_C7") (pin "2") (pinfunction "2_2") (pintype "passive"))
      (node (ref "J1") (pin "19") (pinfunction "19_19") (pintype "bidirectional"))
    )
    (net (code "31") (name "Net-(EPD_C8-Pad2)") (class "Default")
      (node (ref "EPD_C8") (pin "2") (pinfunction "2_2") (pintype "passive"))
      (node (ref "J1") (pin "20") (pinfunction "20_20") (pintype "bidirectional"))
    )
    (net (code "32") (name "Net-(EPD_C9-Pad2)") (class "Default")
      (node (ref "EPD_C9") (pin "2") (pinfunction "2_2") (pintype "passive"))
      (node (ref "J1") (pin "21") (pinfunction "21_21") (pintype "bidirectional"))
    )
    (net (code "33") (name "Net-(EPD_C10-Pad2)") (class "Default")
      (node (ref "EPD_C10") (pin "2") (pinfunction "2_2") (pintype "passive"))
      (node (ref "J1") (pin "22") (pinfunction "22_22") (pintype "bidirectional"))
    )
    (net (code "34") (name "Net-(EPD_C11-Pad2)") (class "Default")
      (node (ref "EPD_C11") (pin "2") (pinfunction "2_2") (pintype "passive"))
      (node (ref "J1") (pin "23") (pinfunction "23_23") (pintype "bidirectional"))
    )
    (net (code "35") (name "Net-(EPD_C12-Pad2)") (class "Default")
      (node (ref "EPD_C12") (pin "2") (pinfunction "2_2") (pintype "passive"))
      (node (ref "J1") (pin "24") (pinfunction "24_24") (pintype "bidirectional"))
    )
    (net (code "36") (name "Net-(IC1-CT)") (class "Default")
      (node (ref "C_DELAY") (pin "1") (pinfunction "1_1") (pintype "passive"))
      (node (ref "IC1") (pin "5") (pinfunction "CT_5") (pintype "bidirectional"))
    )
    (net (code "37") (name "Net-(J2-PadA5)") (class "Default")
      (node (ref "J2") (pin "A5") (pinfunction "A5_A5") (pintype "bidirectional"))
      (node (ref "R2-USB1") (pin "2") (pinfunction "2_2") (pintype "passive"))
    )
    (net (code "38") (name "Net-(J2-PadB5)") (class "Default")
      (node (ref "J2") (pin "B5") (pinfunction "B5_B5") (pintype "bidirectional"))
      (node (ref "R2-USB") (pin "1") (pinfunction "1_1") (pintype "passive"))
    )
    (net (code "39") (name "Net-(MCP73831-PROG)") (class "Default")
      (node (ref "MCP73831") (pin "5") (pinfunction "PROG_5") (pintype "input"))
      (node (ref "R2_BAT") (pin "2") (pinfunction "2_2") (pintype "passive"))
    )
    (net (code "40") (name "Net-(MCP73831-STAT)") (class "Default")
      (node (ref "MCP73831") (pin "1") (pinfunction "STAT_1") (pintype "output"))
      (node (ref "R1_BAT") (pin "2") (pinfunction "2_2") (pintype "passive"))
    )
    (net (code "41") (name "PREVGH") (class "Default")
      (node (ref "D5") (pin "1") (pinfunction "K_1") (pintype "bidirectional"))
    )
    (net (code "42") (name "PREVGL") (class "Default")
      (node (ref "D4") (pin "2") (pinfunction "A_2") (pintype "bidirectional"))
    )
    (net (code "43") (name "RESE") (class "Default")
      (node (ref "J1") (pin "3") (pinfunction "3_3") (pintype "bidirectional"))
      (node (ref "Q3") (pin "2") (pinfunction "S_2") (pintype "bidirectional"))
      (node (ref "R3") (pin "2") (pinfunction "2_2") (pintype "passive"))
    )
    (net (code "44") (name "RESE'") (class "Default")
      (node (ref "R2") (pin "2") (pinfunction "2_2") (pintype "passive"))
      (node (ref "R3") (pin "1") (pinfunction "1_1") (pintype "passive"))
      (node (ref "SJ1") (pin "2") (pinfunction "2_2") (pintype "passive"))
    )
    (net (code "45") (name "RESET") (class "Default")
      (node (ref "C5") (pin "1") (pinfunction "1_1") (pintype "passive"))
      (node (ref "IC1") (pin "1") (pinfunction "VOUT_1") (pintype "bidirectional"))
      (node (ref "RESET_BUTTON") (pin "4") (pinfunction "4_4") (pintype "passive"))
      (node (ref "R_RESET") (pin "1") (pinfunction "1_1") (pintype "passive"))
      (node (ref "U2") (pin "3") (pinfunction "EN_3") (pintype "input"))
    )
    (net (code "46") (name "RTC_RST") (class "Default")
      (node (ref "U2") (pin "16") (pinfunction "IO18_16") (pintype "bidirectional"))
      (node (ref "U3") (pin "4") (pinfunction "~{RST}_4") (pintype "input"))
    )
    (net (code "47") (name "RX") (class "Default")
      (node (ref "TP2") (pin "TP") (pinfunction "TP_TP") (pintype "input"))
      (node (ref "U2") (pin "24") (pinfunction "RXD0/GPIO17_24") (pintype "bidirectional"))
    )
    (net (code "48") (name "SCK") (class "Default")
      (node (ref "D9") (pin "1") (pinfunction "1_1") (pintype "passive"))
      (node (ref "J1") (pin "13") (pinfunction "13_13") (pintype "bidirectional"))
      (node (ref "J4") (pin "P5") (pinfunction "CLK_P5") (pintype "bidirectional"))
      (node (ref "R5") (pin "1") (pinfunction "1_1") (pintype "passive"))
      (node (ref "TP8") (pin "TP") (pinfunction "TP_TP") (pintype "input"))
      (node (ref "U1") (pin "6") (pinfunction "CLK_6") (pintype "input"))
      (node (ref "U2") (pin "6") (pinfunction "IO6_6") (pintype "bidirectional"))
    )
    (net (code "49") (name "SCL") (class "Default")
      (node (ref "J3") (pin "4") (pinfunction "4_4") (pintype "passive"))
      (node (ref "R2_PINH") (pin "1") (pinfunction "1_1") (pintype "passive"))
      (node (ref "SENSOR2") (pin "4") (pinfunction "SCK_4") (pintype "input"))
      (node (ref "U2") (pin "20") (pinfunction "IO22_20") (pintype "bidirectional"))
      (node (ref "U3") (pin "16") (pinfunction "SCL_16") (pintype "input"))
      (node (ref "U4") (pin "7") (pinfunction "SCL_7") (pintype "input"))
    )
    (net (code "50") (name "SDA") (class "Default")
      (node (ref "J3") (pin "3") (pinfunction "3_3") (pintype "passive"))
      (node (ref "R1_PINH") (pin "1") (pinfunction "1_1") (pintype "passive"))
      (node (ref "SENSOR2") (pin "3") (pinfunction "SDI_3") (pintype "bidirectional"))
      (node (ref "U2") (pin "19") (pinfunction "IO21_19") (pintype "bidirectional"))
      (node (ref "U3") (pin "15") (pinfunction "SDA_15") (pintype "bidirectional"))
      (node (ref "U4") (pin "8") (pinfunction "SDA_8") (pintype "bidirectional"))
    )
    (net (code "51") (name "SRC") (class "Default")
      (node (ref "C4") (pin "2") (pinfunction "2_2") (pintype "passive"))
      (node (ref "D5") (pin "2") (pinfunction "A_2") (pintype "bidirectional"))
      (node (ref "L1") (pin "1") (pinfunction "1_1") (pintype "passive"))
      (node (ref "Q3") (pin "3") (pinfunction "D_3") (pintype "bidirectional"))
    )
    (net (code "52") (name "SS_SD") (class "Default")
      (node (ref "J4") (pin "P2") (pinfunction "CD/DAT3_P2") (pintype "bidirectional"))
      (node (ref "U2") (pin "4") (pinfunction "IO4_4") (pintype "bidirectional"))
    )
    (net (code "53") (name "TX") (class "Default")
      (node (ref "TP1") (pin "TP") (pinfunction "TP_TP") (pintype "input"))
      (node (ref "U2") (pin "25") (pinfunction "TXD0/GPIO16_25") (pintype "bidirectional"))
    )
    (net (code "54") (name "USB_D+") (class "Default")
      (node (ref "D1") (pin "1") (pinfunction "I/O1_1_1") (pintype "bidirectional"))
      (node (ref "U2") (pin "14") (pinfunction "IO13_14") (pintype "bidirectional"))
    )
    (net (code "55") (name "USB_D-") (class "Default")
      (node (ref "D1") (pin "3") (pinfunction "I/O2_1_3") (pintype "bidirectional"))
      (node (ref "U2") (pin "13") (pinfunction "IO12_13") (pintype "bidirectional"))
    )
    (net (code "56") (name "VBAT") (class "Default")
      (node (ref "C2_BAT") (pin "1") (pinfunction "1_1") (pintype "passive"))
      (node (ref "MCP73831") (pin "3") (pinfunction "VBAT_3") (pintype "power_in"))
      (node (ref "Q1") (pin "3") (pinfunction "D_3") (pintype "bidirectional"))
      (node (ref "TP3") (pin "TP") (pinfunction "TP_TP") (pintype "input"))
      (node (ref "U4") (pin "2") (pinfunction "CELL_2") (pintype "power_in"))
      (node (ref "U4") (pin "3") (pinfunction "VDD_3") (pintype "power_in"))
    )
    (net (code "57") (name "VBUS") (class "Default")
      (node (ref "C1_BAT") (pin "1") (pinfunction "1_1") (pintype "passive"))
      (node (ref "C4_USB") (pin "1") (pinfunction "1_1") (pintype "passive"))
      (node (ref "C5_USB") (pin "1") (pinfunction "1_1") (pintype "passive"))
      (node (ref "CHG_LED") (pin "A") (pinfunction "A_A") (pintype "passive"))
      (node (ref "D1") (pin "5") (pinfunction "VBUS_5") (pintype "bidirectional"))
      (node (ref "D2") (pin "2") (pinfunction "ANODE_2") (pintype "bidirectional"))
      (node (ref "MCP73831") (pin "4") (pinfunction "VIN_4") (pintype "power_in"))
      (node (ref "PFMF.050.1") (pin "2") (pinfunction "2_2") (pintype "passive"))
      (node (ref "Q1") (pin "1") (pinfunction "G_1") (pintype "bidirectional"))
      (node (ref "R1_PWRUSB") (pin "2") (pinfunction "2_2") (pintype "passive"))
      (node (ref "TP14") (pin "TP") (pinfunction "TP_TP") (pintype "input"))
    )
    (net (code "58") (name "VRTC") (class "Default")
      (node (ref "C10_SUPERCAP") (pin "2") (pinfunction "2_2") (pintype "passive"))
      (node (ref "C8") (pin "1") (pinfunction "1_1") (pintype "passive"))
      (node (ref "R_CAPACITOR") (pin "2") (pinfunction "2_2") (pintype "passive"))
      (node (ref "U3") (pin "14") (pinfunction "VBAT_14") (pintype "power_in"))
    )
    (net (code "59") (name "VUSB") (class "Default")
      (node (ref "J2") (pin "A4") (pinfunction "A4_A4") (pintype "bidirectional"))
      (node (ref "J2") (pin "A9") (pinfunction "A9_A9") (pintype "bidirectional"))
      (node (ref "J2") (pin "B4") (pinfunction "B4_B4") (pintype "bidirectional"))
      (node (ref "J2") (pin "B9") (pinfunction "B9_B9") (pintype "bidirectional"))
      (node (ref "PFMF.050.1") (pin "1") (pinfunction "1_1") (pintype "passive"))
    )
    (net (code "60") (name "unconnected-(BOOT_BUTTON-Pad1)") (class "Default")
      (node (ref "BOOT_BUTTON") (pin "1") (pinfunction "1_1") (pintype "passive"))
    )
    (net (code "61") (name "unconnected-(BOOT_BUTTON-Pad3)") (class "Default")
      (node (ref "BOOT_BUTTON") (pin "3") (pinfunction "3_3") (pintype "passive"))
    )
    (net (code "62") (name "unconnected-(CHANGE_BUTTON-Pad1)") (class "Default")
      (node (ref "CHANGE_BUTTON") (pin "1") (pinfunction "1_1") (pintype "passive"))
    )
    (net (code "63") (name "unconnected-(CHANGE_BUTTON-Pad3)") (class "Default")
      (node (ref "CHANGE_BUTTON") (pin "3") (pinfunction "3_3") (pintype "passive"))
    )
    (net (code "64") (name "unconnected-(IC1-NC-Pad4)") (class "Default")
      (node (ref "IC1") (pin "4") (pinfunction "NC_4") (pintype "no_connect"))
    )
    (net (code "65") (name "unconnected-(IC4-NC-Pad4)") (class "Default")
      (node (ref "IC4") (pin "4") (pinfunction "NC_4") (pintype "no_connect"))
    )
    (net (code "66") (name "unconnected-(J1-Pad1)") (class "Default")
      (node (ref "J1") (pin "1") (pinfunction "1_1") (pintype "bidirectional"))
    )
    (net (code "67") (name "unconnected-(J1-Pad6)") (class "Default")
      (node (ref "J1") (pin "6") (pinfunction "6_6") (pintype "bidirectional"))
    )
    (net (code "68") (name "unconnected-(J1-Pad7)") (class "Default")
      (node (ref "J1") (pin "7") (pinfunction "7_7") (pintype "bidirectional"))
    )
    (net (code "69") (name "unconnected-(J2-PadA8)") (class "Default")
      (node (ref "J2") (pin "A8") (pinfunction "A8_A8") (pintype "bidirectional"))
    )
    (net (code "70") (name "unconnected-(J2-PadB8)") (class "Default")
      (node (ref "J2") (pin "B8") (pinfunction "B8_B8") (pintype "bidirectional"))
    )
    (net (code "71") (name "unconnected-(J4-DAT1-PadP8)") (class "Default")
      (node (ref "J4") (pin "P8") (pinfunction "DAT1_P8") (pintype "bidirectional"))
    )
    (net (code "72") (name "unconnected-(J4-DAT2-PadP1)") (class "Default")
      (node (ref "J4") (pin "P1") (pinfunction "DAT2_P1") (pintype "bidirectional"))
    )
    (net (code "73") (name "unconnected-(J4-DETECTION_1-PadS1)") (class "Default")
      (node (ref "J4") (pin "S1") (pinfunction "DETECTION_1_S1") (pintype "bidirectional"))
    )
    (net (code "74") (name "unconnected-(J4-DETECTION_2-PadS2)") (class "Default")
      (node (ref "J4") (pin "S2") (pinfunction "DETECTION_2_S2") (pintype "bidirectional"))
    )
    (net (code "75") (name "unconnected-(RESET_BUTTON-Pad1)") (class "Default")
      (node (ref "RESET_BUTTON") (pin "1") (pinfunction "1_1") (pintype "passive"))
    )
    (net (code "76") (name "unconnected-(RESET_BUTTON-Pad3)") (class "Default")
      (node (ref "RESET_BUTTON") (pin "3") (pinfunction "3_3") (pintype "passive"))
    )
    (net (code "77") (name "unconnected-(U2-NC-Pad22)") (class "Default")
      (node (ref "U2") (pin "22") (pinfunction "NC_22") (pintype "no_connect"))
    )
    (net (code "78") (name "unconnected-(U4-~{ALERT}-Pad5)") (class "Default")
      (node (ref "U4") (pin "5") (pinfunction "~{ALERT}_5") (pintype "output"))
    )
  )
)
